# untitled.net
KiCad netlist of a schematic drawn in EAGLE
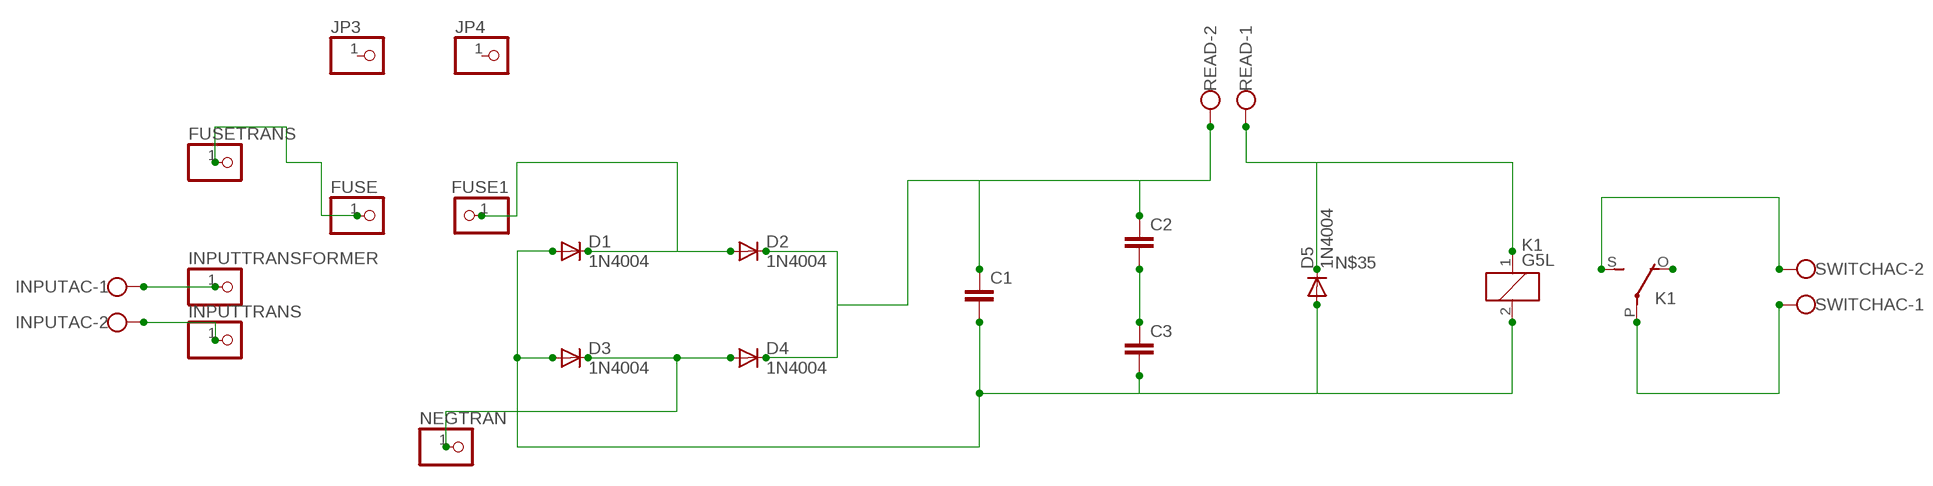
[diagram p0: schematic, sheet 1]

(export (version "E")
  (design (tool "Eeschema 10.0.6"))
  (components
    (comp (ref "C1")
      (value "CAPACITOR050-075X075")
      (footprint "eagle-import:C050-075X075")
      (libsource (lib "eagle-import") (part "CAPACITOR050-075X075"))
    )
    (comp (ref "C2")
      (value "CAPACITOR050-075X075")
      (footprint "eagle-import:C050-075X075")
      (libsource (lib "eagle-import") (part "CAPACITOR050-075X075"))
    )
    (comp (ref "C3")
      (value "CAPACITOR050-075X075")
      (footprint "eagle-import:C050-075X075")
      (libsource (lib "eagle-import") (part "CAPACITOR050-075X075"))
    )
    (comp (ref "D1")
      (value "1N4004")
      (footprint "eagle-import:DO41-10")
      (libsource (lib "eagle-import") (part "1N4004"))
    )
    (comp (ref "D2")
      (value "1N4004")
      (footprint "eagle-import:DO41-10")
      (libsource (lib "eagle-import") (part "1N4004"))
    )
    (comp (ref "D3")
      (value "1N4004")
      (footprint "eagle-import:DO41-10")
      (libsource (lib "eagle-import") (part "1N4004"))
    )
    (comp (ref "D4")
      (value "1N4004")
      (footprint "eagle-import:DO41-10")
      (libsource (lib "eagle-import") (part "1N4004"))
    )
    (comp (ref "D5")
      (value "1N4004")
      (footprint "eagle-import:DO41-10")
      (libsource (lib "eagle-import") (part "1N4004"))
    )
    (comp (ref "FUSE")
      (value "PINHD-1X1")
      (footprint "eagle-import:1X01")
      (libsource (lib "eagle-import") (part "PINHD-1X1"))
    )
    (comp (ref "FUSE1")
      (value "PINHD-1X1")
      (footprint "eagle-import:1X01")
      (libsource (lib "eagle-import") (part "PINHD-1X1"))
    )
    (comp (ref "FUSETRANS")
      (value "PINHD-1X1")
      (footprint "eagle-import:1X01")
      (libsource (lib "eagle-import") (part "PINHD-1X1"))
    )
    (comp (ref "INPUTAC")
      (value "SCREW_TERMINAL_POWER")
      (footprint "eagle-import:POWER_CONNECTOR")
      (fields (field (name "MPN") "237-102"))
      (libsource (lib "eagle-import") (part "SCREW_TERMINAL_POWER"))
    )
    (comp (ref "INPUTTRANS")
      (value "PINHD-1X1")
      (footprint "eagle-import:1X01")
      (libsource (lib "eagle-import") (part "PINHD-1X1"))
    )
    (comp (ref "INPUTTRANSFORMER")
      (value "PINHD-1X1")
      (footprint "eagle-import:1X01")
      (libsource (lib "eagle-import") (part "PINHD-1X1"))
    )
    (comp (ref "JP3")
      (value "PINHD-1X1")
      (footprint "eagle-import:1X01")
      (libsource (lib "eagle-import") (part "PINHD-1X1"))
    )
    (comp (ref "JP4")
      (value "PINHD-1X1")
      (footprint "eagle-import:1X01")
      (libsource (lib "eagle-import") (part "PINHD-1X1"))
    )
    (comp (ref "K1")
      (value "G5L")
      (footprint "eagle-import:G5LE")
      (libsource (lib "eagle-import") (part "G5L"))
    )
    (comp (ref "NEGTRAN")
      (value "PINHD-1X1")
      (footprint "eagle-import:1X01")
      (libsource (lib "eagle-import") (part "PINHD-1X1"))
    )
    (comp (ref "READ")
      (value "SCREW_TERMINAL_POWER")
      (footprint "eagle-import:POWER_CONNECTOR")
      (fields (field (name "MPN") "237-102"))
      (libsource (lib "eagle-import") (part "SCREW_TERMINAL_POWER"))
    )
    (comp (ref "SWITCHAC")
      (value "SCREW_TERMINAL_POWER")
      (footprint "eagle-import:POWER_CONNECTOR")
      (fields (field (name "MPN") "237-102"))
      (libsource (lib "eagle-import") (part "SCREW_TERMINAL_POWER"))
    )
  )
  (nets
    (net (code "1") (name "/N$35") (class "Default")
      (node (ref "D5") (pin "C") (pinfunction "C_C") (pintype "passive"))
      (node (ref "K1") (pin "1") (pinfunction "1_1") (pintype "passive"))
      (node (ref "READ") (pin "1") (pinfunction "KL_1") (pintype "passive"))
    )
    (net (code "2") (name "Net-(C1-Pad2)") (class "Default")
      (node (ref "C1") (pin "2") (pinfunction "2_2") (pintype "passive"))
      (node (ref "C3") (pin "2") (pinfunction "2_2") (pintype "passive"))
      (node (ref "D1") (pin "A") (pinfunction "A_A") (pintype "passive"))
      (node (ref "D3") (pin "A") (pinfunction "A_A") (pintype "passive"))
      (node (ref "D5") (pin "A") (pinfunction "A_A") (pintype "passive"))
      (node (ref "K1") (pin "2") (pinfunction "2_2") (pintype "passive"))
    )
    (net (code "3") (name "Net-(C2-Pad2)") (class "Default")
      (node (ref "C2") (pin "2") (pinfunction "2_2") (pintype "passive"))
      (node (ref "C3") (pin "1") (pinfunction "1_1") (pintype "passive"))
    )
    (net (code "4") (name "Net-(D1-PadC)") (class "Default")
      (node (ref "D1") (pin "C") (pinfunction "C_C") (pintype "passive"))
      (node (ref "D2") (pin "A") (pinfunction "A_A") (pintype "passive"))
      (node (ref "FUSE1") (pin "1") (pinfunction "1_1") (pintype "passive"))
    )
    (net (code "5") (name "Net-(D3-PadC)") (class "Default")
      (node (ref "D3") (pin "C") (pinfunction "C_C") (pintype "passive"))
      (node (ref "D4") (pin "A") (pinfunction "A_A") (pintype "passive"))
      (node (ref "NEGTRAN") (pin "1") (pinfunction "1_1") (pintype "passive"))
    )
    (net (code "6") (name "Net-(FUSE-Pad1)") (class "Default")
      (node (ref "FUSE") (pin "1") (pinfunction "1_1") (pintype "passive"))
      (node (ref "FUSETRANS") (pin "1") (pinfunction "1_1") (pintype "passive"))
    )
    (net (code "7") (name "Net-(INPUTACA-KL)") (class "Default")
      (node (ref "INPUTAC") (pin "1") (pinfunction "KL_1") (pintype "passive"))
      (node (ref "INPUTTRANSFORMER") (pin "1") (pinfunction "1_1") (pintype "passive"))
    )
    (net (code "8") (name "Net-(INPUTACB-KL)") (class "Default")
      (node (ref "INPUTAC") (pin "2") (pinfunction "KL_2") (pintype "passive"))
      (node (ref "INPUTTRANS") (pin "1") (pinfunction "1_1") (pintype "passive"))
    )
    (net (code "9") (name "Net-(READB-KL)") (class "Default")
      (node (ref "C1") (pin "1") (pinfunction "1_1") (pintype "passive"))
      (node (ref "C2") (pin "1") (pinfunction "1_1") (pintype "passive"))
      (node (ref "D2") (pin "C") (pinfunction "C_C") (pintype "passive"))
      (node (ref "D4") (pin "C") (pinfunction "C_C") (pintype "passive"))
      (node (ref "READ") (pin "2") (pinfunction "KL_2") (pintype "passive"))
    )
    (net (code "10") (name "Net-(SWITCHACA-KL)") (class "Default")
      (node (ref "K1") (pin "P") (pinfunction "P_P") (pintype "passive"))
      (node (ref "SWITCHAC") (pin "1") (pinfunction "KL_1") (pintype "passive"))
    )
    (net (code "11") (name "Net-(SWITCHACB-KL)") (class "Default")
      (node (ref "K1") (pin "S") (pinfunction "S_S") (pintype "passive"))
      (node (ref "SWITCHAC") (pin "2") (pinfunction "KL_2") (pintype "passive"))
    )
    (net (code "12") (name "unconnected-(JP3-Pad1)") (class "Default")
      (node (ref "JP3") (pin "1") (pinfunction "1_1") (pintype "passive"))
    )
    (net (code "13") (name "unconnected-(JP4-Pad1)") (class "Default")
      (node (ref "JP4") (pin "1") (pinfunction "1_1") (pintype "passive"))
    )
    (net (code "14") (name "unconnected-(K1-PadO)") (class "Default")
      (node (ref "K1") (pin "O") (pinfunction "O_O") (pintype "passive"))
    )
  )
)
